# LNA.net
KiCad netlist of a schematic drawn in Altium Designer
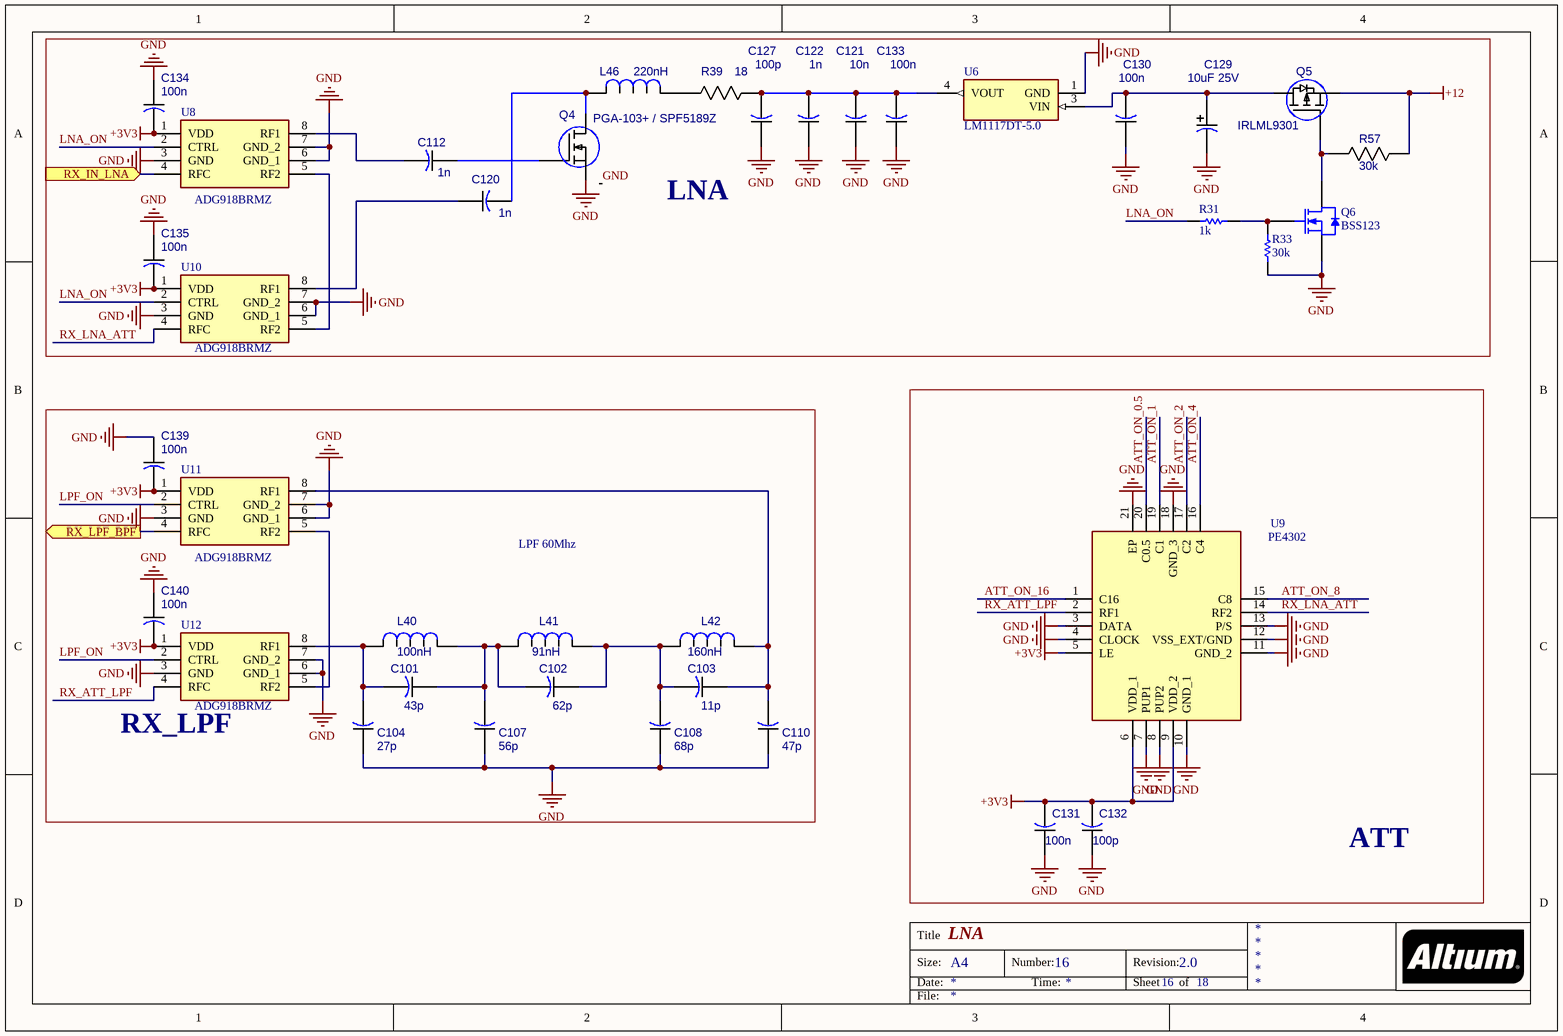
[diagram p0: LNA.SchDoc]

(export (version "E")
  (design (tool "Eeschema 10.0.6"))
  (components
    (comp (ref "C101")
      (value "43p")
      (footprint "CAP_0805")
      (description "CAP_0805")
      (libsource (lib "*") (part "CAP_0805"))
    )
    (comp (ref "C102")
      (value "62p")
      (footprint "CAP_0805")
      (description "CAP_0805")
      (libsource (lib "*") (part "CAP_0805"))
    )
    (comp (ref "C103")
      (value "11p")
      (footprint "CAP_0805")
      (description "CAP_0805")
      (libsource (lib "*") (part "CAP_0805"))
    )
    (comp (ref "C104")
      (value "27p")
      (footprint "CAP_0805")
      (description "CAP_0805")
      (libsource (lib "*") (part "CAP_0805"))
    )
    (comp (ref "C107")
      (value "56p")
      (footprint "CAP_0805")
      (description "CAP_0805")
      (libsource (lib "*") (part "CAP_0805"))
    )
    (comp (ref "C108")
      (value "68p")
      (footprint "CAP_0805")
      (description "CAP_0805")
      (libsource (lib "*") (part "CAP_0805"))
    )
    (comp (ref "C110")
      (value "47p")
      (footprint "CAP_0805")
      (description "CAP_0805")
      (libsource (lib "*") (part "CAP_0805"))
    )
    (comp (ref "C112")
      (value "1n")
      (footprint "CAP_0805")
      (description "CAP_0805")
      (libsource (lib "*") (part "CAP_0805"))
    )
    (comp (ref "C120")
      (value "1n")
      (footprint "CAP_0805")
      (description "CAP_0805")
      (libsource (lib "*") (part "CAP_0805"))
    )
    (comp (ref "C121")
      (value "10n")
      (footprint "6-0805_M")
      (description "CAP_0805")
      (libsource (lib "*") (part "CAP_0805"))
    )
    (comp (ref "C122")
      (value "1n")
      (footprint "6-0805_M")
      (description "CAP_0805")
      (libsource (lib "*") (part "CAP_0805"))
    )
    (comp (ref "C127")
      (value "100p")
      (footprint "6-0805_M")
      (description "CAP_0805")
      (libsource (lib "*") (part "CAP_0805"))
    )
    (comp (ref "C129")
      (value "10uF 25V")
      (footprint "CAPAE_5.3x5.3h6.1")
      (description "CAPAE_5.3x5.3h6.1")
      (libsource (lib "*") (part "CAPAE_5.3x5.3h6.1"))
    )
    (comp (ref "C130")
      (value "100n")
      (footprint "CAP_0805")
      (description "CAP_0805")
      (libsource (lib "") (part "CAP_0805_1"))
    )
    (comp (ref "C131")
      (value "100n")
      (footprint "6-0805_M")
      (description "CAP_0805")
      (libsource (lib "*") (part "CAP_0805"))
    )
    (comp (ref "C132")
      (value "100p")
      (footprint "6-0805_M")
      (description "CAP_0805")
      (libsource (lib "*") (part "CAP_0805"))
    )
    (comp (ref "C133")
      (value "100n")
      (footprint "CAP_0805")
      (description "CAP_0805")
      (libsource (lib "*") (part "CAP_0805"))
    )
    (comp (ref "C134")
      (value "100n")
      (footprint "CAP_0805")
      (description "CAP_0805")
      (libsource (lib "*") (part "CAP_0805"))
    )
    (comp (ref "C135")
      (value "100n")
      (footprint "CAP_0805")
      (description "CAP_0805")
      (libsource (lib "*") (part "CAP_0805"))
    )
    (comp (ref "C139")
      (value "100n")
      (footprint "CAP_0805")
      (description "CAP_0805")
      (libsource (lib "*") (part "CAP_0805"))
    )
    (comp (ref "C140")
      (value "100n")
      (footprint "CAP_0805")
      (description "CAP_0805")
      (libsource (lib "*") (part "CAP_0805"))
    )
    (comp (ref "L40")
      (value "100nH")
      (footprint "IND_0805")
      (description "IND_0805")
      (libsource (lib "*") (part "IND_0805"))
    )
    (comp (ref "L41")
      (value "91nH")
      (footprint "IND_0805")
      (description "IND_0805")
      (libsource (lib "*") (part "IND_0805"))
    )
    (comp (ref "L42")
      (value "160nH")
      (footprint "IND_0805")
      (description "IND_0805")
      (libsource (lib "*") (part "IND_0805"))
    )
    (comp (ref "L46")
      (value "220nH")
      (footprint "IND_1206")
      (description "IND_1206")
      (libsource (lib "*") (part "IND_1206"))
    )
    (comp (ref "Q4")
      (value "PGA-103+ / SPF5189Z")
      (footprint "SOT89")
      (libsource (lib "*") (part "PGA-103+"))
    )
    (comp (ref "Q5")
      (value "IRLML9301")
      (footprint "SOT23")
      (description "MOSFET")
      (libsource (lib "*") (part "MOSFET_ENH_PD"))
    )
    (comp (ref "Q6")
      (value "BSS123")
      (footprint "FAIR-SOT23-3_V")
      (fields (field (name "MANUFACTURER") "Fairchild"))
      (libsource (lib "Altium Content Vault") (part "NEMOS-GSD-3"))
    )
    (comp (ref "R31")
      (value "1k")
      (footprint "RESC2013X60X40NL20T25")
      (description "RES_0805")
      (fields (field (name "MANUFACTURER") "Panasonic") (field (name "PART NUMBER") "ERA-6AEB303V"))
      (libsource (lib "Altium Content Vault") (part "RES"))
    )
    (comp (ref "R33")
      (value "30k")
      (footprint "RESC2013X60X40NL20T25")
      (description "RES_0805")
      (fields (field (name "MANUFACTURER") "Panasonic") (field (name "PART NUMBER") "ERA-6AEB303V"))
      (libsource (lib "Altium Content Vault") (part "RES"))
    )
    (comp (ref "R39")
      (value "18")
      (footprint "RES_1206")
      (description "RES_1206")
      (libsource (lib "*") (part "RES_1206"))
    )
    (comp (ref "R57")
      (value "30k")
      (footprint "RES_0805")
      (description "RES_0805")
      (libsource (lib "*") (part "RES_0805"))
    )
    (comp (ref "U6")
      (value "LM1117DT-5.0")
      (footprint "SamacSys:TO228P991X238-3N")
      (description "Integrated Circuit")
      (fields
        (field (name "MANUFACTURER_PART_NUMBER") "LM1117DT-ADJ")
        (field (name "MOUSER PART NUMBER") "926-LM1117DT-ADJ")
      )
      (libsource (lib "*") (part "LM1117DT-ADJ"))
    )
    (comp (ref "U8")
      (value "ADG918BRMZ")
      (footprint "SamacSys:SOP65P490X110-8N")
      (description "Integrated Circuit")
      (fields (field (name "MOUSER PART NUMBER") "584-ADG918BRMZ") (field (name "RS PART NUMBER") "4969212P"))
      (libsource (lib "*") (part "ADG918BRMZ"))
    )
    (comp (ref "U9")
      (value "PE4302")
      (footprint "SamacSys:QFN50P400X400X90-21N")
      (description "Integrated Circuit")
      (fields (field (name "MANUFACTURER_PART_NUMBER") "PE4312C-Z"))
      (libsource (lib "*") (part "PE4312C-Z"))
    )
    (comp (ref "U10")
      (value "ADG918BRMZ")
      (footprint "SamacSys:SOP65P490X110-8N")
      (description "Integrated Circuit")
      (fields (field (name "MOUSER PART NUMBER") "584-ADG918BRMZ") (field (name "RS PART NUMBER") "4969212P"))
      (libsource (lib "*") (part "ADG918BRMZ"))
    )
    (comp (ref "U11")
      (value "ADG918BRMZ")
      (footprint "SamacSys:SOP65P490X110-8N")
      (description "Integrated Circuit")
      (fields (field (name "MOUSER PART NUMBER") "584-ADG918BRMZ") (field (name "RS PART NUMBER") "4969212P"))
      (libsource (lib "*") (part "ADG918BRMZ"))
    )
    (comp (ref "U12")
      (value "ADG918BRMZ")
      (footprint "SamacSys:SOP65P490X110-8N")
      (description "Integrated Circuit")
      (fields (field (name "MOUSER PART NUMBER") "584-ADG918BRMZ") (field (name "RS PART NUMBER") "4969212P"))
      (libsource (lib "*") (part "ADG918BRMZ"))
    )
  )
  (nets
    (net (code "1") (name "+3V3") (class "Default")
      (node (ref "C131") (pin "2") (pinfunction "2_2") (pintype "passive"))
      (node (ref "C132") (pin "2") (pinfunction "2_2") (pintype "passive"))
      (node (ref "C134") (pin "2") (pinfunction "2_2") (pintype "passive"))
      (node (ref "C135") (pin "2") (pinfunction "2_2") (pintype "passive"))
      (node (ref "C139") (pin "2") (pinfunction "2_2") (pintype "passive"))
      (node (ref "C140") (pin "2") (pinfunction "2_2") (pintype "passive"))
      (node (ref "U10") (pin "1") (pinfunction "VDD_1") (pintype "power_in"))
      (node (ref "U11") (pin "1") (pinfunction "VDD_1") (pintype "power_in"))
      (node (ref "U12") (pin "1") (pinfunction "VDD_1") (pintype "power_in"))
      (node (ref "U8") (pin "1") (pinfunction "VDD_1") (pintype "power_in"))
      (node (ref "U9") (pin "5") (pinfunction "LE_5") (pintype "passive"))
      (node (ref "U9") (pin "6") (pinfunction "VDD_1_6") (pintype "passive"))
      (node (ref "U9") (pin "9") (pinfunction "VDD_2_9") (pintype "passive"))
    )
    (net (code "2") (name "+12") (class "Default")
      (node (ref "Q5") (pin "2") (pinfunction "S_2") (pintype "passive"))
      (node (ref "R57") (pin "2") (pinfunction "2_2") (pintype "passive"))
    )
    (net (code "3") (name "/ATT_ON_0.5") (class "Default")
      (node (ref "U9") (pin "20") (pinfunction "C0.5_20") (pintype "passive"))
    )
    (net (code "4") (name "/ATT_ON_1") (class "Default")
      (node (ref "U9") (pin "19") (pinfunction "C1_19") (pintype "passive"))
    )
    (net (code "5") (name "/ATT_ON_2") (class "Default")
      (node (ref "U9") (pin "17") (pinfunction "C2_17") (pintype "passive"))
    )
    (net (code "6") (name "/ATT_ON_4") (class "Default")
      (node (ref "U9") (pin "16") (pinfunction "C4_16") (pintype "passive"))
    )
    (net (code "7") (name "/ATT_ON_8") (class "Default")
      (node (ref "U9") (pin "15") (pinfunction "C8_15") (pintype "passive"))
    )
    (net (code "8") (name "/ATT_ON_16") (class "Default")
      (node (ref "U9") (pin "1") (pinfunction "C16_1") (pintype "passive"))
    )
    (net (code "9") (name "/LNA_ON") (class "Default")
      (node (ref "R31") (pin "2") (pinfunction "2_2") (pintype "passive"))
      (node (ref "U10") (pin "2") (pinfunction "CTRL_2") (pintype "passive"))
      (node (ref "U8") (pin "2") (pinfunction "CTRL_2") (pintype "passive"))
    )
    (net (code "10") (name "/LPF_ON") (class "Default")
      (node (ref "U11") (pin "2") (pinfunction "CTRL_2") (pintype "passive"))
      (node (ref "U12") (pin "2") (pinfunction "CTRL_2") (pintype "passive"))
    )
    (net (code "11") (name "/RX_ATT_LPF") (class "Default")
      (node (ref "U12") (pin "4") (pinfunction "RFC_4") (pintype "passive"))
      (node (ref "U9") (pin "2") (pinfunction "RF1_2") (pintype "passive"))
    )
    (net (code "12") (name "/RX_IN_LNA") (class "Default")
      (node (ref "U8") (pin "4") (pinfunction "RFC_4") (pintype "passive"))
    )
    (net (code "13") (name "/RX_LNA_ATT") (class "Default")
      (node (ref "U10") (pin "4") (pinfunction "RFC_4") (pintype "passive"))
      (node (ref "U9") (pin "14") (pinfunction "RF2_14") (pintype "passive"))
    )
    (net (code "14") (name "/RX_LPF_BPF") (class "Default")
      (node (ref "U11") (pin "4") (pinfunction "RFC_4") (pintype "passive"))
    )
    (net (code "15") (name "GND") (class "Default")
      (node (ref "C104") (pin "1") (pinfunction "1_1") (pintype "passive"))
      (node (ref "C107") (pin "1") (pinfunction "1_1") (pintype "passive"))
      (node (ref "C108") (pin "1") (pinfunction "1_1") (pintype "passive"))
      (node (ref "C110") (pin "1") (pinfunction "1_1") (pintype "passive"))
      (node (ref "C121") (pin "1") (pinfunction "1_1") (pintype "passive"))
      (node (ref "C122") (pin "1") (pinfunction "1_1") (pintype "passive"))
      (node (ref "C127") (pin "1") (pinfunction "1_1") (pintype "passive"))
      (node (ref "C129") (pin "2") (pinfunction "MINUS_2") (pintype "passive"))
      (node (ref "C130") (pin "1") (pinfunction "1_1") (pintype "passive"))
      (node (ref "C131") (pin "1") (pinfunction "1_1") (pintype "passive"))
      (node (ref "C132") (pin "1") (pinfunction "1_1") (pintype "passive"))
      (node (ref "C133") (pin "1") (pinfunction "1_1") (pintype "passive"))
      (node (ref "C134") (pin "1") (pinfunction "1_1") (pintype "passive"))
      (node (ref "C135") (pin "1") (pinfunction "1_1") (pintype "passive"))
      (node (ref "C139") (pin "1") (pinfunction "1_1") (pintype "passive"))
      (node (ref "C140") (pin "1") (pinfunction "1_1") (pintype "passive"))
      (node (ref "Q4") (pin "0") (pinfunction "0_0") (pintype "passive"))
      (node (ref "Q4") (pin "2") (pinfunction "S_2") (pintype "passive"))
      (node (ref "Q6") (pin "2") (pinfunction "S_2") (pintype "passive"))
      (node (ref "R33") (pin "1") (pinfunction "1_1") (pintype "passive"))
      (node (ref "U10") (pin "3") (pinfunction "GND_3") (pintype "power_in"))
      (node (ref "U10") (pin "6") (pinfunction "GND_1_6") (pintype "power_in"))
      (node (ref "U10") (pin "7") (pinfunction "GND_2_7") (pintype "power_in"))
      (node (ref "U11") (pin "3") (pinfunction "GND_3") (pintype "power_in"))
      (node (ref "U11") (pin "6") (pinfunction "GND_1_6") (pintype "power_in"))
      (node (ref "U11") (pin "7") (pinfunction "GND_2_7") (pintype "power_in"))
      (node (ref "U12") (pin "3") (pinfunction "GND_3") (pintype "power_in"))
      (node (ref "U12") (pin "6") (pinfunction "GND_1_6") (pintype "power_in"))
      (node (ref "U12") (pin "7") (pinfunction "GND_2_7") (pintype "power_in"))
      (node (ref "U6") (pin "1") (pinfunction "GND_1") (pintype "passive"))
      (node (ref "U8") (pin "3") (pinfunction "GND_3") (pintype "power_in"))
      (node (ref "U8") (pin "6") (pinfunction "GND_1_6") (pintype "power_in"))
      (node (ref "U8") (pin "7") (pinfunction "GND_2_7") (pintype "power_in"))
      (node (ref "U9") (pin "10") (pinfunction "GND_1_10") (pintype "passive"))
      (node (ref "U9") (pin "11") (pinfunction "GND_2_11") (pintype "passive"))
      (node (ref "U9") (pin "12") (pinfunction "VSS_EXT/GND_12") (pintype "passive"))
      (node (ref "U9") (pin "13") (pinfunction "P/S_13") (pintype "passive"))
      (node (ref "U9") (pin "18") (pinfunction "GND_3_18") (pintype "passive"))
      (node (ref "U9") (pin "21") (pinfunction "EP_21") (pintype "passive"))
      (node (ref "U9") (pin "3") (pinfunction "DATA_3") (pintype "passive"))
      (node (ref "U9") (pin "4") (pinfunction "CLOCK_4") (pintype "passive"))
      (node (ref "U9") (pin "7") (pinfunction "PUP1_7") (pintype "passive"))
      (node (ref "U9") (pin "8") (pinfunction "PUP2_8") (pintype "passive"))
    )
    (net (code "16") (name "Net-(C101-Pad1)") (class "Default")
      (node (ref "C101") (pin "1") (pinfunction "1_1") (pintype "passive"))
      (node (ref "C102") (pin "2") (pinfunction "2_2") (pintype "passive"))
      (node (ref "C107") (pin "2") (pinfunction "2_2") (pintype "passive"))
      (node (ref "L40") (pin "2") (pinfunction "2_2") (pintype "passive"))
      (node (ref "L41") (pin "1") (pinfunction "1_1") (pintype "passive"))
    )
    (net (code "17") (name "Net-(C102-Pad1)") (class "Default")
      (node (ref "C102") (pin "1") (pinfunction "1_1") (pintype "passive"))
      (node (ref "C103") (pin "2") (pinfunction "2_2") (pintype "passive"))
      (node (ref "C108") (pin "2") (pinfunction "2_2") (pintype "passive"))
      (node (ref "L41") (pin "2") (pinfunction "2_2") (pintype "passive"))
      (node (ref "L42") (pin "1") (pinfunction "1_1") (pintype "passive"))
    )
    (net (code "18") (name "Net-(C129-PLUS)") (class "Default")
      (node (ref "C129") (pin "1") (pinfunction "PLUS_1") (pintype "passive"))
      (node (ref "C130") (pin "2") (pinfunction "2_2") (pintype "passive"))
      (node (ref "Q5") (pin "3") (pinfunction "D_3") (pintype "passive"))
      (node (ref "U6") (pin "3") (pinfunction "VIN_3") (pintype "input"))
    )
    (net (code "19") (name "Net-(L46-1)") (class "Default")
      (node (ref "C120") (pin "2") (pinfunction "2_2") (pintype "passive"))
      (node (ref "L46") (pin "2") (pinfunction "1_2") (pintype "passive"))
      (node (ref "Q4") (pin "3") (pinfunction "D_3") (pintype "passive"))
    )
    (net (code "20") (name "Net-(L46-2)") (class "Default")
      (node (ref "L46") (pin "1") (pinfunction "2_1") (pintype "passive"))
      (node (ref "R39") (pin "2") (pinfunction "2_2") (pintype "passive"))
    )
    (net (code "21") (name "Net-(Q4-G)") (class "Default")
      (node (ref "C112") (pin "1") (pinfunction "1_1") (pintype "passive"))
      (node (ref "Q4") (pin "1") (pinfunction "G_1") (pintype "passive"))
    )
    (net (code "22") (name "Net-(Q5-G)") (class "Default")
      (node (ref "Q5") (pin "1") (pinfunction "G_1") (pintype "passive"))
      (node (ref "Q6") (pin "3") (pinfunction "D_3") (pintype "passive"))
      (node (ref "R57") (pin "1") (pinfunction "1_1") (pintype "passive"))
    )
    (net (code "23") (name "Net-(Q6-G)") (class "Default")
      (node (ref "Q6") (pin "1") (pinfunction "G_1") (pintype "passive"))
      (node (ref "R31") (pin "1") (pinfunction "1_1") (pintype "passive"))
      (node (ref "R33") (pin "2") (pinfunction "2_2") (pintype "passive"))
    )
    (net (code "24") (name "Net-(U6-VOUT)") (class "Default")
      (node (ref "C121") (pin "2") (pinfunction "2_2") (pintype "passive"))
      (node (ref "C122") (pin "2") (pinfunction "2_2") (pintype "passive"))
      (node (ref "C127") (pin "2") (pinfunction "2_2") (pintype "passive"))
      (node (ref "C133") (pin "2") (pinfunction "2_2") (pintype "passive"))
      (node (ref "R39") (pin "1") (pinfunction "1_1") (pintype "passive"))
      (node (ref "U6") (pin "4") (pinfunction "VOUT_4") (pintype "output"))
    )
    (net (code "25") (name "Net-(U8-RF1)") (class "Default")
      (node (ref "C112") (pin "2") (pinfunction "2_2") (pintype "passive"))
      (node (ref "U8") (pin "8") (pinfunction "RF1_8") (pintype "passive"))
    )
    (net (code "26") (name "Net-(U10-RF1)") (class "Default")
      (node (ref "C120") (pin "1") (pinfunction "1_1") (pintype "passive"))
      (node (ref "U10") (pin "8") (pinfunction "RF1_8") (pintype "passive"))
    )
    (net (code "27") (name "Net-(U10-RF2)") (class "Default")
      (node (ref "U10") (pin "5") (pinfunction "RF2_5") (pintype "passive"))
      (node (ref "U8") (pin "5") (pinfunction "RF2_5") (pintype "passive"))
    )
    (net (code "28") (name "Net-(U11-RF1)") (class "Default")
      (node (ref "C103") (pin "1") (pinfunction "1_1") (pintype "passive"))
      (node (ref "C110") (pin "2") (pinfunction "2_2") (pintype "passive"))
      (node (ref "L42") (pin "2") (pinfunction "2_2") (pintype "passive"))
      (node (ref "U11") (pin "8") (pinfunction "RF1_8") (pintype "passive"))
    )
    (net (code "29") (name "Net-(U11-RF2)") (class "Default")
      (node (ref "U11") (pin "5") (pinfunction "RF2_5") (pintype "passive"))
      (node (ref "U12") (pin "5") (pinfunction "RF2_5") (pintype "passive"))
    )
    (net (code "30") (name "Net-(U12-RF1)") (class "Default")
      (node (ref "C101") (pin "2") (pinfunction "2_2") (pintype "passive"))
      (node (ref "C104") (pin "2") (pinfunction "2_2") (pintype "passive"))
      (node (ref "L40") (pin "1") (pinfunction "1_1") (pintype "passive"))
      (node (ref "U12") (pin "8") (pinfunction "RF1_8") (pintype "passive"))
    )
  )
)
